# fatina.net
KiCad netlist of a schematic drawn in EAGLE
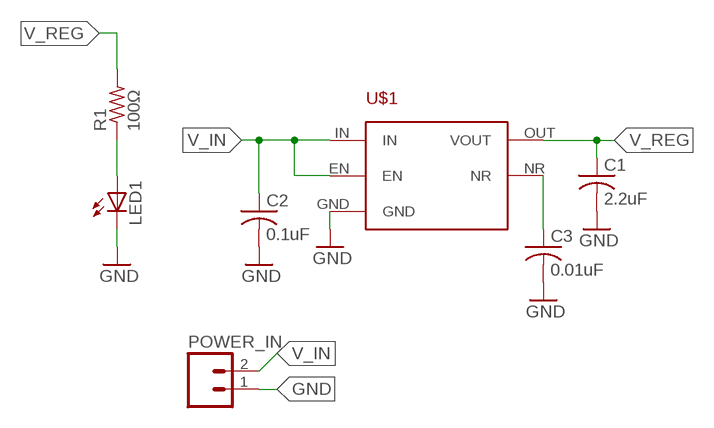
[diagram p0: schematic, sheet 1]

(export (version "E")
  (design (tool "Eeschema 10.0.6"))
  (components
    (comp (ref "C1")
      (value "2.2uF")
      (footprint "eagle-import:C0603")
      (libsource (lib "eagle-import") (part "C-USC0603"))
    )
    (comp (ref "C2")
      (value "0.1uF")
      (footprint "eagle-import:C0603")
      (libsource (lib "eagle-import") (part "C-USC0603"))
    )
    (comp (ref "C3")
      (value "0.01uF")
      (footprint "eagle-import:C0603")
      (libsource (lib "eagle-import") (part "C-USC0603"))
    )
    (comp (ref "LED1")
      (value "LED5MM")
      (footprint "eagle-import:LED5MM")
      (libsource (lib "eagle-import") (part "LED5MM"))
    )
    (comp (ref "POWER_IN")
      (value "M02PTH")
      (footprint "eagle-import:1X02")
      (libsource (lib "eagle-import") (part "M02PTH"))
    )
    (comp (ref "R1")
      (value "100Ω")
      (footprint "eagle-import:0204_7")
      (libsource (lib "eagle-import") (part "R-US_0204/7"))
    )
    (comp (ref "U$1")
      (value "TPS799")
      (footprint "eagle-import:TPS799")
      (libsource (lib "eagle-import") (part "TPS799"))
    )
  )
  (nets
    (net (code "1") (name "GND") (class "Default")
      (node (ref "C1") (pin "2") (pinfunction "2_2") (pintype "passive"))
      (node (ref "C2") (pin "2") (pinfunction "2_2") (pintype "passive"))
      (node (ref "C3") (pin "2") (pinfunction "2_2") (pintype "passive"))
      (node (ref "LED1") (pin "K") (pinfunction "C_K") (pintype "passive"))
      (node (ref "POWER_IN") (pin "1") (pinfunction "1_1") (pintype "passive"))
      (node (ref "U$1") (pin "GND") (pinfunction "GND_GND") (pintype "power_in"))
    )
    (net (code "2") (name "Net-(C3-Pad1)") (class "Default")
      (node (ref "C3") (pin "1") (pinfunction "1_1") (pintype "passive"))
      (node (ref "U$1") (pin "NR") (pinfunction "NR_NR") (pintype "output"))
    )
    (net (code "3") (name "Net-(LED1-PadA)") (class "Default")
      (node (ref "LED1") (pin "A") (pinfunction "A_A") (pintype "passive"))
      (node (ref "R1") (pin "1") (pinfunction "1_1") (pintype "passive"))
    )
    (net (code "4") (name "V_IN") (class "Default")
      (node (ref "C2") (pin "1") (pinfunction "1_1") (pintype "passive"))
      (node (ref "POWER_IN") (pin "2") (pinfunction "2_2") (pintype "passive"))
      (node (ref "U$1") (pin "EN") (pinfunction "EN_EN") (pintype "input"))
      (node (ref "U$1") (pin "IN") (pinfunction "IN_IN") (pintype "power_in"))
    )
    (net (code "5") (name "V_REG") (class "Default")
      (node (ref "C1") (pin "1") (pinfunction "1_1") (pintype "passive"))
      (node (ref "R1") (pin "2") (pinfunction "2_2") (pintype "passive"))
      (node (ref "U$1") (pin "OUT") (pinfunction "VOUT_OUT") (pintype "output"))
    )
  )
)
